# kapcs.net
KiCad netlist of a schematic drawn in EAGLE
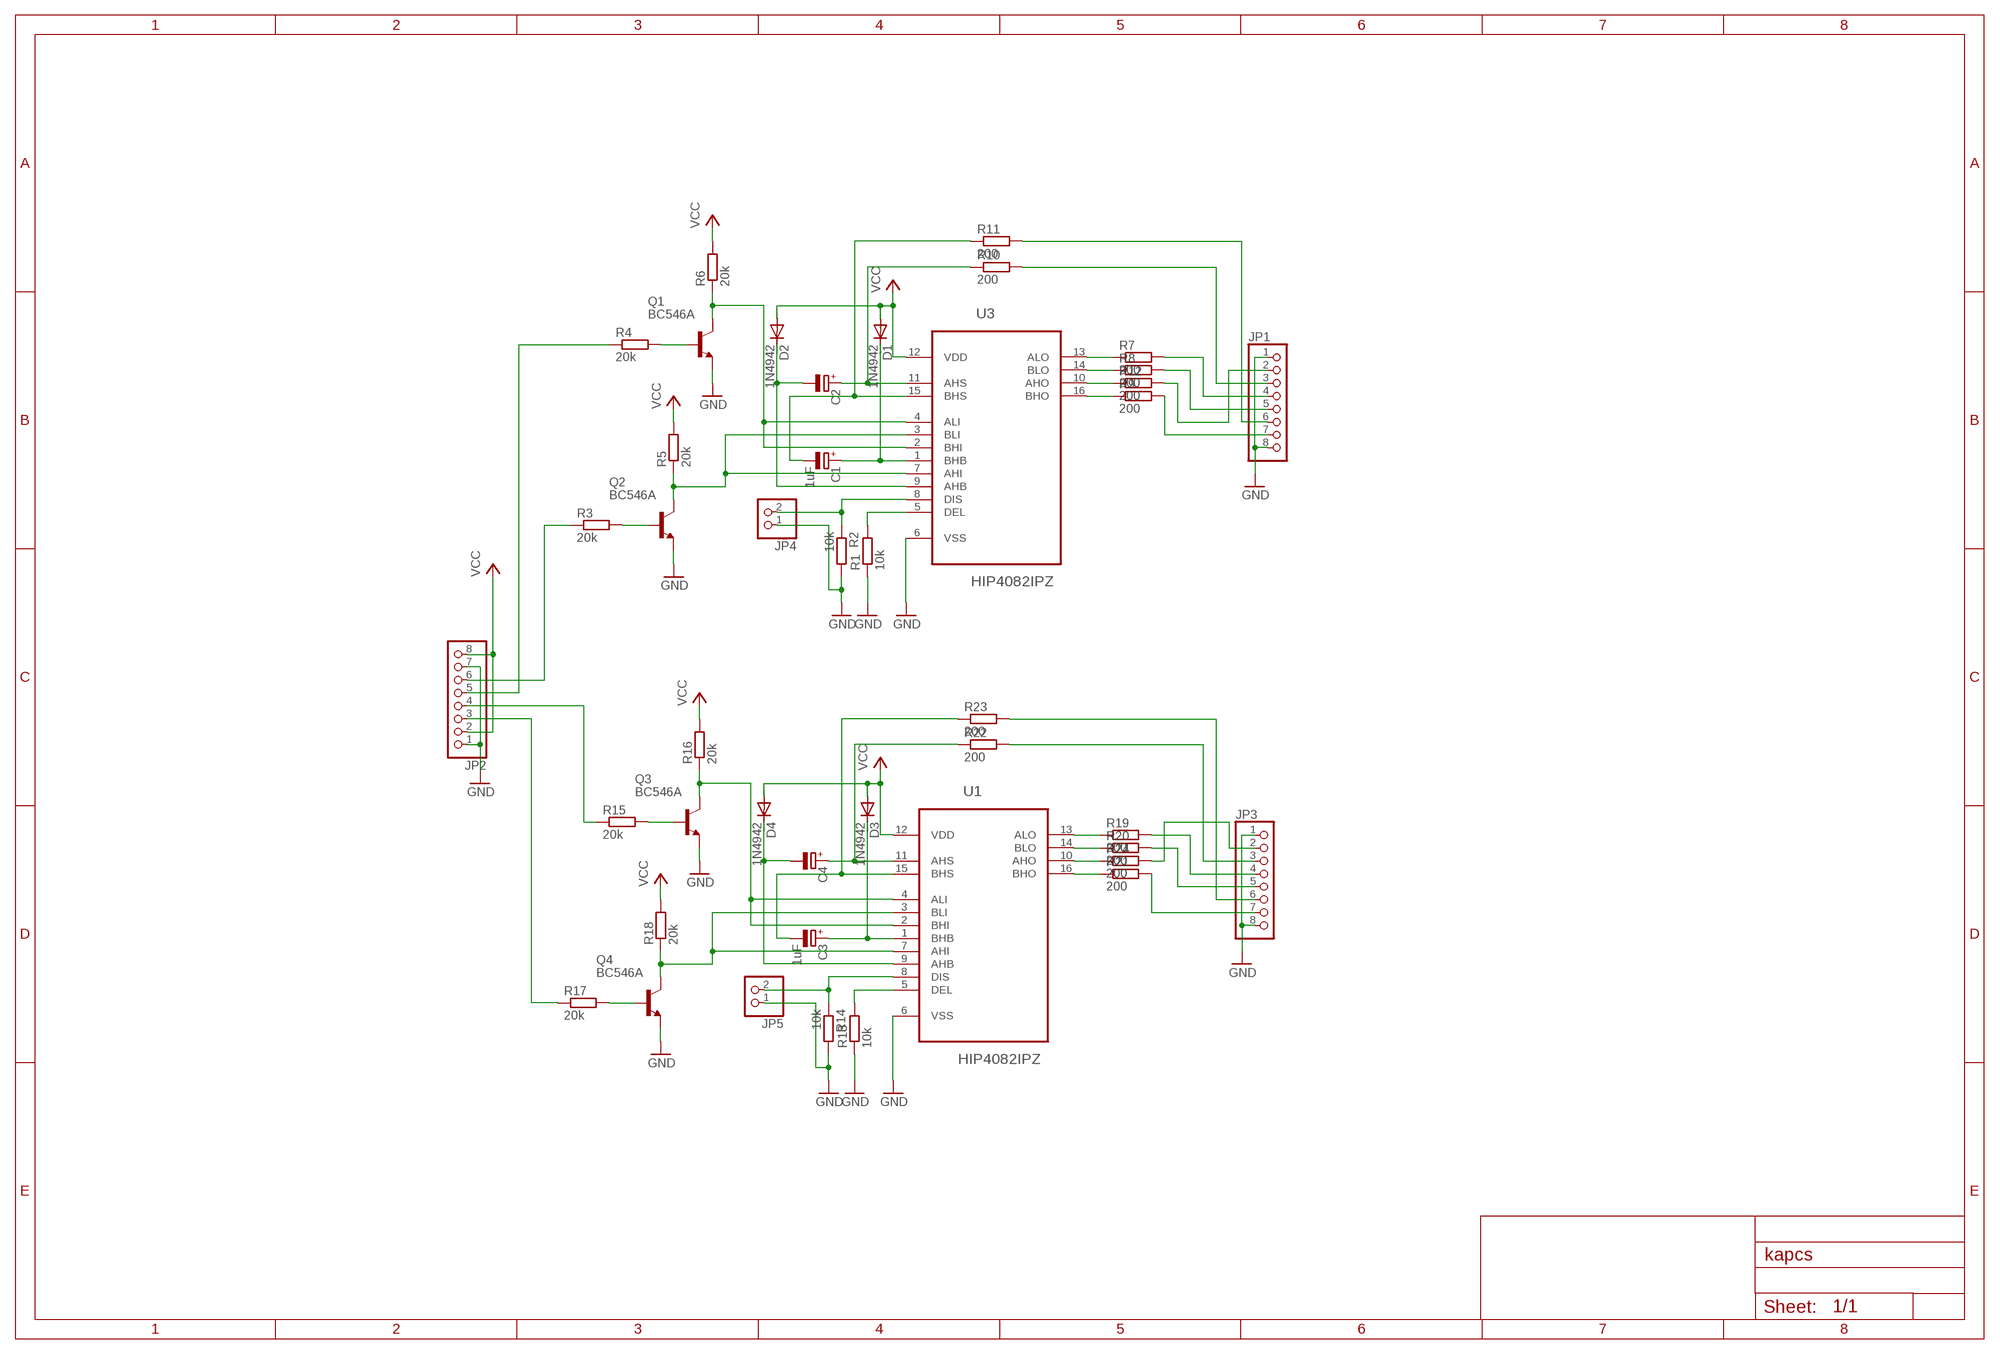
[diagram p0: schematic, sheet 1]

(export (version "E")
  (design (tool "Eeschema 10.0.6"))
  (components
    (comp (ref "C1")
      (value "1uF")
      (footprint "eagle-import:E2,5-5")
      (libsource (lib "eagle-import") (part "CPOL-EUE2.5-5"))
    )
    (comp (ref "C2")
      (value "CPOL-EUE2.5-5")
      (footprint "eagle-import:E2,5-5")
      (libsource (lib "eagle-import") (part "CPOL-EUE2.5-5"))
    )
    (comp (ref "C3")
      (value "1uF")
      (footprint "eagle-import:E2,5-5")
      (libsource (lib "eagle-import") (part "CPOL-EUE2.5-5"))
    )
    (comp (ref "C4")
      (value "CPOL-EUE2.5-5")
      (footprint "eagle-import:E2,5-5")
      (libsource (lib "eagle-import") (part "CPOL-EUE2.5-5"))
    )
    (comp (ref "D1")
      (value "1N4942")
      (footprint "eagle-import:DO41-10")
      (libsource (lib "eagle-import") (part "1N4942"))
    )
    (comp (ref "D2")
      (value "1N4942")
      (footprint "eagle-import:DO41-10")
      (libsource (lib "eagle-import") (part "1N4942"))
    )
    (comp (ref "D3")
      (value "1N4942")
      (footprint "eagle-import:DO41-10")
      (libsource (lib "eagle-import") (part "1N4942"))
    )
    (comp (ref "D4")
      (value "1N4942")
      (footprint "eagle-import:DO41-10")
      (libsource (lib "eagle-import") (part "1N4942"))
    )
    (comp (ref "JP1")
      (value "PINHD-1X8")
      (footprint "eagle-import:1X08")
      (libsource (lib "eagle-import") (part "PINHD-1X8"))
    )
    (comp (ref "JP2")
      (value "PINHD-1X8")
      (footprint "eagle-import:1X08")
      (libsource (lib "eagle-import") (part "PINHD-1X8"))
    )
    (comp (ref "JP3")
      (value "PINHD-1X8")
      (footprint "eagle-import:1X08")
      (libsource (lib "eagle-import") (part "PINHD-1X8"))
    )
    (comp (ref "JP4")
      (value "PINHD-1X2")
      (footprint "eagle-import:1X02")
      (libsource (lib "eagle-import") (part "PINHD-1X2"))
    )
    (comp (ref "JP5")
      (value "PINHD-1X2")
      (footprint "eagle-import:1X02")
      (libsource (lib "eagle-import") (part "PINHD-1X2"))
    )
    (comp (ref "Q1")
      (value "BC546A")
      (footprint "eagle-import:TO92-EBC")
      (libsource (lib "eagle-import") (part "BC546A"))
    )
    (comp (ref "Q2")
      (value "BC546A")
      (footprint "eagle-import:TO92-EBC")
      (libsource (lib "eagle-import") (part "BC546A"))
    )
    (comp (ref "Q3")
      (value "BC546A")
      (footprint "eagle-import:TO92-EBC")
      (libsource (lib "eagle-import") (part "BC546A"))
    )
    (comp (ref "Q4")
      (value "BC546A")
      (footprint "eagle-import:TO92-EBC")
      (libsource (lib "eagle-import") (part "BC546A"))
    )
    (comp (ref "R1")
      (value "10k")
      (footprint "eagle-import:0207_7")
      (libsource (lib "eagle-import") (part "R-EU_0207/7"))
    )
    (comp (ref "R2")
      (value "10k")
      (footprint "eagle-import:0207_7")
      (libsource (lib "eagle-import") (part "R-EU_0207/7"))
    )
    (comp (ref "R3")
      (value "20k")
      (footprint "eagle-import:0207_7")
      (libsource (lib "eagle-import") (part "R-EU_0207/7"))
    )
    (comp (ref "R4")
      (value "20k")
      (footprint "eagle-import:0207_7")
      (libsource (lib "eagle-import") (part "R-EU_0207/7"))
    )
    (comp (ref "R5")
      (value "20k")
      (footprint "eagle-import:0207_7")
      (libsource (lib "eagle-import") (part "R-EU_0207/7"))
    )
    (comp (ref "R6")
      (value "20k")
      (footprint "eagle-import:0207_7")
      (libsource (lib "eagle-import") (part "R-EU_0207/7"))
    )
    (comp (ref "R7")
      (value "200")
      (footprint "eagle-import:0207_7")
      (libsource (lib "eagle-import") (part "R-EU_0207/7"))
    )
    (comp (ref "R8")
      (value "200")
      (footprint "eagle-import:0207_7")
      (libsource (lib "eagle-import") (part "R-EU_0207/7"))
    )
    (comp (ref "R9")
      (value "200")
      (footprint "eagle-import:0207_7")
      (libsource (lib "eagle-import") (part "R-EU_0207/7"))
    )
    (comp (ref "R10")
      (value "200")
      (footprint "eagle-import:0207_7")
      (libsource (lib "eagle-import") (part "R-EU_0207/7"))
    )
    (comp (ref "R11")
      (value "200")
      (footprint "eagle-import:0207_7")
      (libsource (lib "eagle-import") (part "R-EU_0207/7"))
    )
    (comp (ref "R12")
      (value "200")
      (footprint "eagle-import:0207_7")
      (libsource (lib "eagle-import") (part "R-EU_0207/7"))
    )
    (comp (ref "R13")
      (value "10k")
      (footprint "eagle-import:0207_7")
      (libsource (lib "eagle-import") (part "R-EU_0207/7"))
    )
    (comp (ref "R14")
      (value "10k")
      (footprint "eagle-import:0207_7")
      (libsource (lib "eagle-import") (part "R-EU_0207/7"))
    )
    (comp (ref "R15")
      (value "20k")
      (footprint "eagle-import:0207_7")
      (libsource (lib "eagle-import") (part "R-EU_0207/7"))
    )
    (comp (ref "R16")
      (value "20k")
      (footprint "eagle-import:0207_7")
      (libsource (lib "eagle-import") (part "R-EU_0207/7"))
    )
    (comp (ref "R17")
      (value "20k")
      (footprint "eagle-import:0207_7")
      (libsource (lib "eagle-import") (part "R-EU_0207/7"))
    )
    (comp (ref "R18")
      (value "20k")
      (footprint "eagle-import:0207_7")
      (libsource (lib "eagle-import") (part "R-EU_0207/7"))
    )
    (comp (ref "R19")
      (value "200")
      (footprint "eagle-import:0207_7")
      (libsource (lib "eagle-import") (part "R-EU_0207/7"))
    )
    (comp (ref "R20")
      (value "200")
      (footprint "eagle-import:0207_7")
      (libsource (lib "eagle-import") (part "R-EU_0207/7"))
    )
    (comp (ref "R21")
      (value "200")
      (footprint "eagle-import:0207_7")
      (libsource (lib "eagle-import") (part "R-EU_0207/7"))
    )
    (comp (ref "R22")
      (value "200")
      (footprint "eagle-import:0207_7")
      (libsource (lib "eagle-import") (part "R-EU_0207/7"))
    )
    (comp (ref "R23")
      (value "200")
      (footprint "eagle-import:0207_7")
      (libsource (lib "eagle-import") (part "R-EU_0207/7"))
    )
    (comp (ref "R24")
      (value "200")
      (footprint "eagle-import:0207_7")
      (libsource (lib "eagle-import") (part "R-EU_0207/7"))
    )
    (comp (ref "U1")
      (value "HIP4082IPZ")
      (footprint "eagle-import:DIP254P762X533-16")
      (libsource (lib "eagle-import") (part "HIP4082IPZ"))
    )
    (comp (ref "U3")
      (value "HIP4082IPZ")
      (footprint "eagle-import:DIP254P762X533-16")
      (libsource (lib "eagle-import") (part "HIP4082IPZ"))
    )
  )
  (nets
    (net (code "1") (name "GND") (class "Default")
      (node (ref "JP1") (pin "1") (pinfunction "1_1") (pintype "passive"))
      (node (ref "JP1") (pin "8") (pinfunction "8_8") (pintype "passive"))
      (node (ref "JP2") (pin "1") (pinfunction "1_1") (pintype "passive"))
      (node (ref "JP2") (pin "7") (pinfunction "7_7") (pintype "passive"))
      (node (ref "JP3") (pin "1") (pinfunction "1_1") (pintype "passive"))
      (node (ref "JP3") (pin "8") (pinfunction "8_8") (pintype "passive"))
      (node (ref "JP4") (pin "1") (pinfunction "1_1") (pintype "passive"))
      (node (ref "JP5") (pin "1") (pinfunction "1_1") (pintype "passive"))
      (node (ref "Q1") (pin "E") (pinfunction "E_E") (pintype "passive"))
      (node (ref "Q2") (pin "E") (pinfunction "E_E") (pintype "passive"))
      (node (ref "Q3") (pin "E") (pinfunction "E_E") (pintype "passive"))
      (node (ref "Q4") (pin "E") (pinfunction "E_E") (pintype "passive"))
      (node (ref "R1") (pin "1") (pinfunction "1_1") (pintype "passive"))
      (node (ref "R13") (pin "1") (pinfunction "1_1") (pintype "passive"))
      (node (ref "R14") (pin "2") (pinfunction "2_2") (pintype "passive"))
      (node (ref "R2") (pin "2") (pinfunction "2_2") (pintype "passive"))
      (node (ref "U1") (pin "6") (pinfunction "VSS_6") (pintype "power_in"))
      (node (ref "U3") (pin "6") (pinfunction "VSS_6") (pintype "power_in"))
    )
    (net (code "2") (name "Net-(JP1-Pad2)") (class "Default")
      (node (ref "JP1") (pin "2") (pinfunction "2_2") (pintype "passive"))
      (node (ref "R12") (pin "2") (pinfunction "2_2") (pintype "passive"))
    )
    (net (code "3") (name "Net-(JP1-Pad3)") (class "Default")
      (node (ref "JP1") (pin "3") (pinfunction "3_3") (pintype "passive"))
      (node (ref "R10") (pin "2") (pinfunction "2_2") (pintype "passive"))
    )
    (net (code "4") (name "Net-(JP1-Pad4)") (class "Default")
      (node (ref "JP1") (pin "4") (pinfunction "4_4") (pintype "passive"))
      (node (ref "R7") (pin "2") (pinfunction "2_2") (pintype "passive"))
    )
    (net (code "5") (name "Net-(JP1-Pad5)") (class "Default")
      (node (ref "JP1") (pin "5") (pinfunction "5_5") (pintype "passive"))
      (node (ref "R8") (pin "2") (pinfunction "2_2") (pintype "passive"))
    )
    (net (code "6") (name "Net-(JP1-Pad6)") (class "Default")
      (node (ref "JP1") (pin "6") (pinfunction "6_6") (pintype "passive"))
      (node (ref "R11") (pin "2") (pinfunction "2_2") (pintype "passive"))
    )
    (net (code "7") (name "Net-(JP1-Pad7)") (class "Default")
      (node (ref "JP1") (pin "7") (pinfunction "7_7") (pintype "passive"))
      (node (ref "R9") (pin "2") (pinfunction "2_2") (pintype "passive"))
    )
    (net (code "8") (name "Net-(JP2-Pad3)") (class "Default")
      (node (ref "JP2") (pin "3") (pinfunction "3_3") (pintype "passive"))
      (node (ref "R17") (pin "1") (pinfunction "1_1") (pintype "passive"))
    )
    (net (code "9") (name "Net-(JP2-Pad4)") (class "Default")
      (node (ref "JP2") (pin "4") (pinfunction "4_4") (pintype "passive"))
      (node (ref "R15") (pin "1") (pinfunction "1_1") (pintype "passive"))
    )
    (net (code "10") (name "Net-(JP2-Pad5)") (class "Default")
      (node (ref "JP2") (pin "5") (pinfunction "5_5") (pintype "passive"))
      (node (ref "R4") (pin "1") (pinfunction "1_1") (pintype "passive"))
    )
    (net (code "11") (name "Net-(JP2-Pad6)") (class "Default")
      (node (ref "JP2") (pin "6") (pinfunction "6_6") (pintype "passive"))
      (node (ref "R3") (pin "1") (pinfunction "1_1") (pintype "passive"))
    )
    (net (code "12") (name "Net-(JP3-Pad2)") (class "Default")
      (node (ref "JP3") (pin "2") (pinfunction "2_2") (pintype "passive"))
      (node (ref "R24") (pin "2") (pinfunction "2_2") (pintype "passive"))
    )
    (net (code "13") (name "Net-(JP3-Pad3)") (class "Default")
      (node (ref "JP3") (pin "3") (pinfunction "3_3") (pintype "passive"))
      (node (ref "R22") (pin "2") (pinfunction "2_2") (pintype "passive"))
    )
    (net (code "14") (name "Net-(JP3-Pad4)") (class "Default")
      (node (ref "JP3") (pin "4") (pinfunction "4_4") (pintype "passive"))
      (node (ref "R19") (pin "2") (pinfunction "2_2") (pintype "passive"))
    )
    (net (code "15") (name "Net-(JP3-Pad5)") (class "Default")
      (node (ref "JP3") (pin "5") (pinfunction "5_5") (pintype "passive"))
      (node (ref "R20") (pin "2") (pinfunction "2_2") (pintype "passive"))
    )
    (net (code "16") (name "Net-(JP3-Pad6)") (class "Default")
      (node (ref "JP3") (pin "6") (pinfunction "6_6") (pintype "passive"))
      (node (ref "R23") (pin "2") (pinfunction "2_2") (pintype "passive"))
    )
    (net (code "17") (name "Net-(JP3-Pad7)") (class "Default")
      (node (ref "JP3") (pin "7") (pinfunction "7_7") (pintype "passive"))
      (node (ref "R21") (pin "2") (pinfunction "2_2") (pintype "passive"))
    )
    (net (code "18") (name "Net-(Q1-PadB)") (class "Default")
      (node (ref "Q1") (pin "B") (pinfunction "B_B") (pintype "passive"))
      (node (ref "R4") (pin "2") (pinfunction "2_2") (pintype "passive"))
    )
    (net (code "19") (name "Net-(Q2-PadB)") (class "Default")
      (node (ref "Q2") (pin "B") (pinfunction "B_B") (pintype "passive"))
      (node (ref "R3") (pin "2") (pinfunction "2_2") (pintype "passive"))
    )
    (net (code "20") (name "Net-(Q3-PadB)") (class "Default")
      (node (ref "Q3") (pin "B") (pinfunction "B_B") (pintype "passive"))
      (node (ref "R15") (pin "2") (pinfunction "2_2") (pintype "passive"))
    )
    (net (code "21") (name "Net-(Q4-PadB)") (class "Default")
      (node (ref "Q4") (pin "B") (pinfunction "B_B") (pintype "passive"))
      (node (ref "R17") (pin "2") (pinfunction "2_2") (pintype "passive"))
    )
    (net (code "22") (name "Net-(U1-AHB)") (class "Default")
      (node (ref "C4") (pin "-") (pinfunction "-_-") (pintype "passive"))
      (node (ref "D4") (pin "C") (pinfunction "C_C") (pintype "passive"))
      (node (ref "U1") (pin "9") (pinfunction "AHB_9") (pintype "input"))
    )
    (net (code "23") (name "Net-(U1-AHI)") (class "Default")
      (node (ref "Q4") (pin "C") (pinfunction "C_C") (pintype "passive"))
      (node (ref "R18") (pin "1") (pinfunction "1_1") (pintype "passive"))
      (node (ref "U1") (pin "3") (pinfunction "BLI_3") (pintype "input"))
      (node (ref "U1") (pin "7") (pinfunction "AHI_7") (pintype "input"))
    )
    (net (code "24") (name "Net-(U1-AHO)") (class "Default")
      (node (ref "R24") (pin "1") (pinfunction "1_1") (pintype "passive"))
      (node (ref "U1") (pin "10") (pinfunction "AHO_10") (pintype "output"))
    )
    (net (code "25") (name "Net-(U1-AHS)") (class "Default")
      (node (ref "C4") (pin "+") (pinfunction "+_+") (pintype "passive"))
      (node (ref "R22") (pin "1") (pinfunction "1_1") (pintype "passive"))
      (node (ref "U1") (pin "11") (pinfunction "AHS_11") (pintype "input"))
    )
    (net (code "26") (name "Net-(U1-ALI)") (class "Default")
      (node (ref "Q3") (pin "C") (pinfunction "C_C") (pintype "passive"))
      (node (ref "R16") (pin "1") (pinfunction "1_1") (pintype "passive"))
      (node (ref "U1") (pin "2") (pinfunction "BHI_2") (pintype "input"))
      (node (ref "U1") (pin "4") (pinfunction "ALI_4") (pintype "input"))
    )
    (net (code "27") (name "Net-(U1-ALO)") (class "Default")
      (node (ref "R19") (pin "1") (pinfunction "1_1") (pintype "passive"))
      (node (ref "U1") (pin "13") (pinfunction "ALO_13") (pintype "output"))
    )
    (net (code "28") (name "Net-(U1-BHB)") (class "Default")
      (node (ref "C3") (pin "+") (pinfunction "+_+") (pintype "passive"))
      (node (ref "D3") (pin "C") (pinfunction "C_C") (pintype "passive"))
      (node (ref "U1") (pin "1") (pinfunction "BHB_1") (pintype "power_in"))
    )
    (net (code "29") (name "Net-(U1-BHO)") (class "Default")
      (node (ref "R21") (pin "1") (pinfunction "1_1") (pintype "passive"))
      (node (ref "U1") (pin "16") (pinfunction "BHO_16") (pintype "output"))
    )
    (net (code "30") (name "Net-(U1-BHS)") (class "Default")
      (node (ref "C3") (pin "-") (pinfunction "-_-") (pintype "passive"))
      (node (ref "R23") (pin "1") (pinfunction "1_1") (pintype "passive"))
      (node (ref "U1") (pin "15") (pinfunction "BHS_15") (pintype "input"))
    )
    (net (code "31") (name "Net-(U1-BLO)") (class "Default")
      (node (ref "R20") (pin "1") (pinfunction "1_1") (pintype "passive"))
      (node (ref "U1") (pin "14") (pinfunction "BLO_14") (pintype "output"))
    )
    (net (code "32") (name "Net-(U1-DEL)") (class "Default")
      (node (ref "R13") (pin "2") (pinfunction "2_2") (pintype "passive"))
      (node (ref "U1") (pin "5") (pinfunction "DEL_5") (pintype "passive"))
    )
    (net (code "33") (name "Net-(U1-DIS)") (class "Default")
      (node (ref "JP5") (pin "2") (pinfunction "2_2") (pintype "passive"))
      (node (ref "R14") (pin "1") (pinfunction "1_1") (pintype "passive"))
      (node (ref "U1") (pin "8") (pinfunction "DIS_8") (pintype "input"))
    )
    (net (code "34") (name "Net-(U3-AHB)") (class "Default")
      (node (ref "C2") (pin "-") (pinfunction "-_-") (pintype "passive"))
      (node (ref "D2") (pin "C") (pinfunction "C_C") (pintype "passive"))
      (node (ref "U3") (pin "9") (pinfunction "AHB_9") (pintype "input"))
    )
    (net (code "35") (name "Net-(U3-AHI)") (class "Default")
      (node (ref "Q2") (pin "C") (pinfunction "C_C") (pintype "passive"))
      (node (ref "R5") (pin "1") (pinfunction "1_1") (pintype "passive"))
      (node (ref "U3") (pin "3") (pinfunction "BLI_3") (pintype "input"))
      (node (ref "U3") (pin "7") (pinfunction "AHI_7") (pintype "input"))
    )
    (net (code "36") (name "Net-(U3-AHO)") (class "Default")
      (node (ref "R12") (pin "1") (pinfunction "1_1") (pintype "passive"))
      (node (ref "U3") (pin "10") (pinfunction "AHO_10") (pintype "output"))
    )
    (net (code "37") (name "Net-(U3-AHS)") (class "Default")
      (node (ref "C2") (pin "+") (pinfunction "+_+") (pintype "passive"))
      (node (ref "R10") (pin "1") (pinfunction "1_1") (pintype "passive"))
      (node (ref "U3") (pin "11") (pinfunction "AHS_11") (pintype "input"))
    )
    (net (code "38") (name "Net-(U3-ALI)") (class "Default")
      (node (ref "Q1") (pin "C") (pinfunction "C_C") (pintype "passive"))
      (node (ref "R6") (pin "1") (pinfunction "1_1") (pintype "passive"))
      (node (ref "U3") (pin "2") (pinfunction "BHI_2") (pintype "input"))
      (node (ref "U3") (pin "4") (pinfunction "ALI_4") (pintype "input"))
    )
    (net (code "39") (name "Net-(U3-ALO)") (class "Default")
      (node (ref "R7") (pin "1") (pinfunction "1_1") (pintype "passive"))
      (node (ref "U3") (pin "13") (pinfunction "ALO_13") (pintype "output"))
    )
    (net (code "40") (name "Net-(U3-BHB)") (class "Default")
      (node (ref "C1") (pin "+") (pinfunction "+_+") (pintype "passive"))
      (node (ref "D1") (pin "C") (pinfunction "C_C") (pintype "passive"))
      (node (ref "U3") (pin "1") (pinfunction "BHB_1") (pintype "power_in"))
    )
    (net (code "41") (name "Net-(U3-BHO)") (class "Default")
      (node (ref "R9") (pin "1") (pinfunction "1_1") (pintype "passive"))
      (node (ref "U3") (pin "16") (pinfunction "BHO_16") (pintype "output"))
    )
    (net (code "42") (name "Net-(U3-BHS)") (class "Default")
      (node (ref "C1") (pin "-") (pinfunction "-_-") (pintype "passive"))
      (node (ref "R11") (pin "1") (pinfunction "1_1") (pintype "passive"))
      (node (ref "U3") (pin "15") (pinfunction "BHS_15") (pintype "input"))
    )
    (net (code "43") (name "Net-(U3-BLO)") (class "Default")
      (node (ref "R8") (pin "1") (pinfunction "1_1") (pintype "passive"))
      (node (ref "U3") (pin "14") (pinfunction "BLO_14") (pintype "output"))
    )
    (net (code "44") (name "Net-(U3-DEL)") (class "Default")
      (node (ref "R1") (pin "2") (pinfunction "2_2") (pintype "passive"))
      (node (ref "U3") (pin "5") (pinfunction "DEL_5") (pintype "passive"))
    )
    (net (code "45") (name "Net-(U3-DIS)") (class "Default")
      (node (ref "JP4") (pin "2") (pinfunction "2_2") (pintype "passive"))
      (node (ref "R2") (pin "1") (pinfunction "1_1") (pintype "passive"))
      (node (ref "U3") (pin "8") (pinfunction "DIS_8") (pintype "input"))
    )
    (net (code "46") (name "VCC") (class "Default")
      (node (ref "D1") (pin "A") (pinfunction "A_A") (pintype "passive"))
      (node (ref "D2") (pin "A") (pinfunction "A_A") (pintype "passive"))
      (node (ref "D3") (pin "A") (pinfunction "A_A") (pintype "passive"))
      (node (ref "D4") (pin "A") (pinfunction "A_A") (pintype "passive"))
      (node (ref "JP2") (pin "2") (pinfunction "2_2") (pintype "passive"))
      (node (ref "JP2") (pin "8") (pinfunction "8_8") (pintype "passive"))
      (node (ref "R16") (pin "2") (pinfunction "2_2") (pintype "passive"))
      (node (ref "R18") (pin "2") (pinfunction "2_2") (pintype "passive"))
      (node (ref "R5") (pin "2") (pinfunction "2_2") (pintype "passive"))
      (node (ref "R6") (pin "2") (pinfunction "2_2") (pintype "passive"))
      (node (ref "U1") (pin "12") (pinfunction "VDD_12") (pintype "power_in"))
      (node (ref "U3") (pin "12") (pinfunction "VDD_12") (pintype "power_in"))
    )
  )
)
